# base_board6.net
KiCad netlist of a schematic drawn in EAGLE
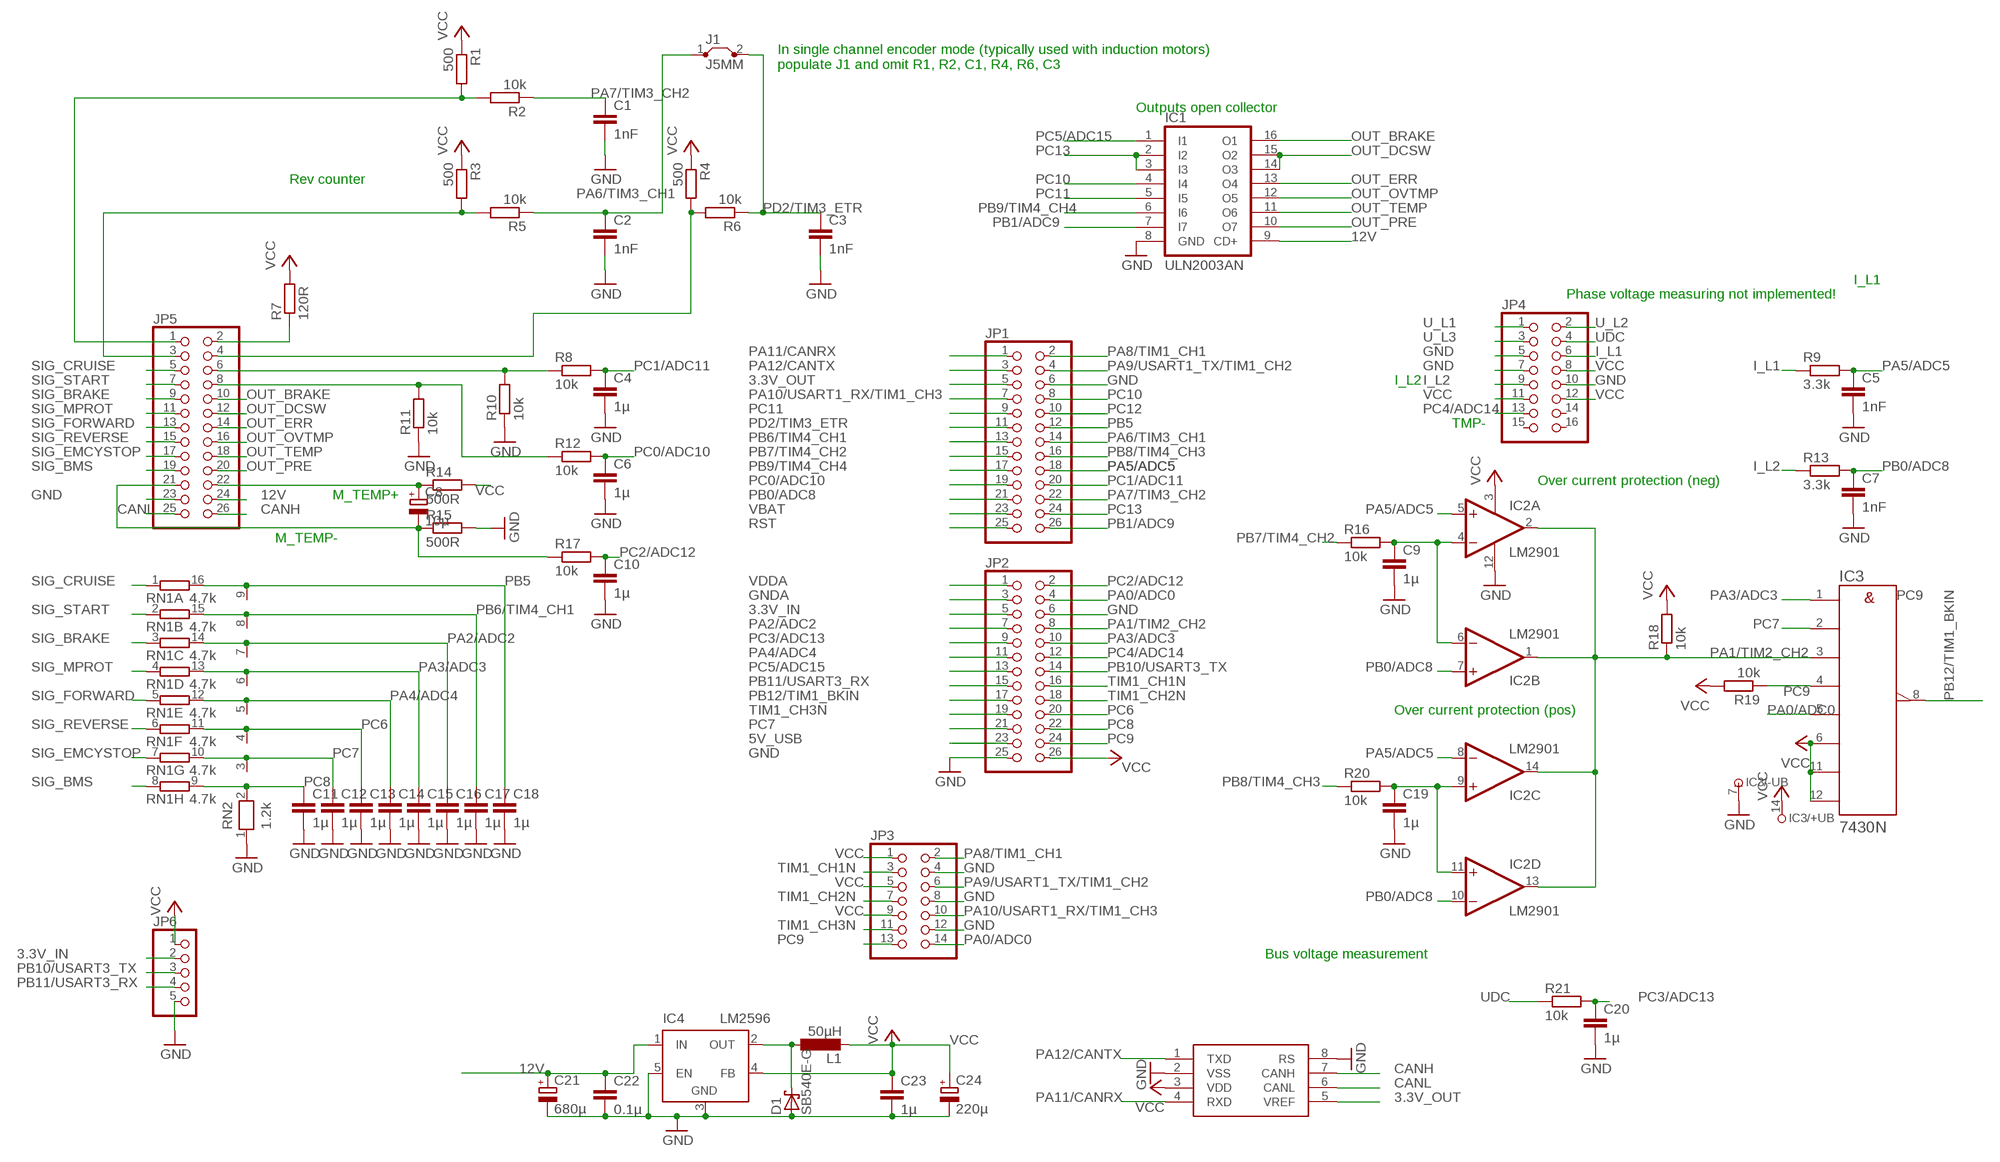
[diagram p0: schematic, sheet 1]

(export (version "E")
  (design (tool "Eeschema 10.0.6"))
  (components
    (comp (ref "C1")
      (value "1nF")
      (footprint "eagle-import:C025-024X044")
      (libsource (lib "eagle-import") (part "C-EU025-024X044"))
    )
    (comp (ref "C2")
      (value "1nF")
      (footprint "eagle-import:C025-024X044")
      (libsource (lib "eagle-import") (part "C-EU025-024X044"))
    )
    (comp (ref "C3")
      (value "1nF")
      (footprint "eagle-import:C025-024X044")
      (libsource (lib "eagle-import") (part "C-EU025-024X044"))
    )
    (comp (ref "C4")
      (value "1µ")
      (footprint "eagle-import:C025-024X044")
      (libsource (lib "eagle-import") (part "C-EU025-024X044"))
    )
    (comp (ref "C5")
      (value "1nF")
      (footprint "eagle-import:C025-024X044")
      (libsource (lib "eagle-import") (part "C-EU025-024X044"))
    )
    (comp (ref "C6")
      (value "1µ")
      (footprint "eagle-import:C025-024X044")
      (libsource (lib "eagle-import") (part "C-EU025-024X044"))
    )
    (comp (ref "C7")
      (value "1nF")
      (footprint "eagle-import:C025-024X044")
      (libsource (lib "eagle-import") (part "C-EU025-024X044"))
    )
    (comp (ref "C8")
      (value "10µ")
      (footprint "eagle-import:E2-4")
      (libsource (lib "eagle-import") (part "CPOL-EUE2-4"))
    )
    (comp (ref "C9")
      (value "1µ")
      (footprint "eagle-import:C025-024X044")
      (libsource (lib "eagle-import") (part "C-EU025-024X044"))
    )
    (comp (ref "C10")
      (value "1µ")
      (footprint "eagle-import:C025-024X044")
      (libsource (lib "eagle-import") (part "C-EU025-024X044"))
    )
    (comp (ref "C11")
      (value "1µ")
      (footprint "eagle-import:C025-024X044")
      (libsource (lib "eagle-import") (part "C-EU025-024X044"))
    )
    (comp (ref "C12")
      (value "1µ")
      (footprint "eagle-import:C025-024X044")
      (libsource (lib "eagle-import") (part "C-EU025-024X044"))
    )
    (comp (ref "C13")
      (value "1µ")
      (footprint "eagle-import:C025-024X044")
      (libsource (lib "eagle-import") (part "C-EU025-024X044"))
    )
    (comp (ref "C14")
      (value "1µ")
      (footprint "eagle-import:C025-024X044")
      (libsource (lib "eagle-import") (part "C-EU025-024X044"))
    )
    (comp (ref "C15")
      (value "1µ")
      (footprint "eagle-import:C025-024X044")
      (libsource (lib "eagle-import") (part "C-EU025-024X044"))
    )
    (comp (ref "C16")
      (value "1µ")
      (footprint "eagle-import:C025-024X044")
      (libsource (lib "eagle-import") (part "C-EU025-024X044"))
    )
    (comp (ref "C17")
      (value "1µ")
      (footprint "eagle-import:C025-024X044")
      (libsource (lib "eagle-import") (part "C-EU025-024X044"))
    )
    (comp (ref "C18")
      (value "1µ")
      (footprint "eagle-import:C025-024X044")
      (libsource (lib "eagle-import") (part "C-EU025-024X044"))
    )
    (comp (ref "C19")
      (value "1µ")
      (footprint "eagle-import:C025-024X044")
      (libsource (lib "eagle-import") (part "C-EU025-024X044"))
    )
    (comp (ref "C20")
      (value "1µ")
      (footprint "eagle-import:C025-024X044")
      (libsource (lib "eagle-import") (part "C-EU025-024X044"))
    )
    (comp (ref "C21")
      (value "680µ")
      (footprint "eagle-import:E2,5-5")
      (libsource (lib "eagle-import") (part "CPOL-EUE2.5-5"))
    )
    (comp (ref "C22")
      (value "0.1µ")
      (footprint "eagle-import:C050-024X044")
      (libsource (lib "eagle-import") (part "C-EU050-024X044"))
    )
    (comp (ref "C23")
      (value "1µ")
      (footprint "eagle-import:C025-024X044")
      (libsource (lib "eagle-import") (part "C-EU025-024X044"))
    )
    (comp (ref "C24")
      (value "220µ")
      (footprint "eagle-import:E2-4")
      (libsource (lib "eagle-import") (part "CPOL-EUE2-4"))
    )
    (comp (ref "D1")
      (value "SB540E-G")
      (footprint "eagle-import:DO201T15")
      (libsource (lib "eagle-import") (part "SCHOTTKY-DIODEDO201T15"))
    )
    (comp (ref "IC1")
      (value "ULN2003AN")
      (footprint "eagle-import:DIL16")
      (libsource (lib "eagle-import") (part "ULN2001AN"))
    )
    (comp (ref "IC2")
      (value "LM2901")
      (footprint "eagle-import:DIL14")
      (libsource (lib "eagle-import") (part "LM339N"))
    )
    (comp (ref "IC3")
      (value "7430N")
      (footprint "eagle-import:DIL14")
      (libsource (lib "eagle-import") (part "7430N"))
    )
    (comp (ref "IC4")
      (value "LM2596")
      (footprint "eagle-import:TO220-51")
      (libsource (lib "eagle-import") (part "LM2596TV"))
    )
    (comp (ref "IC5")
      (value "MCP2562P")
      (footprint "eagle-import:DIL08")
      (libsource (lib "eagle-import") (part "MCP2551P"))
    )
    (comp (ref "J1")
      (value "J5MM")
      (footprint "eagle-import:05")
      (libsource (lib "eagle-import") (part "J5MM"))
    )
    (comp (ref "JP1")
      (value "PINHD-2X13")
      (footprint "eagle-import:2X13")
      (libsource (lib "eagle-import") (part "PINHD-2X13"))
    )
    (comp (ref "JP2")
      (value "PINHD-2X13")
      (footprint "eagle-import:2X13")
      (libsource (lib "eagle-import") (part "PINHD-2X13"))
    )
    (comp (ref "JP3")
      (value "PINHD-2X7")
      (footprint "eagle-import:2X07")
      (libsource (lib "eagle-import") (part "PINHD-2X7"))
    )
    (comp (ref "JP4")
      (value "PINHD-2X8")
      (footprint "eagle-import:2X08")
      (libsource (lib "eagle-import") (part "PINHD-2X8"))
    )
    (comp (ref "JP5")
      (value "PINHD-2X13")
      (footprint "eagle-import:2X13")
      (libsource (lib "eagle-import") (part "PINHD-2X13"))
    )
    (comp (ref "JP6")
      (value "PINHD-1X5")
      (footprint "eagle-import:1X05")
      (libsource (lib "eagle-import") (part "PINHD-1X5"))
    )
    (comp (ref "L1")
      (value "50µH")
      (footprint "eagle-import:TJ3-U1")
      (libsource (lib "eagle-import") (part "L-EUTJ3-U1"))
    )
    (comp (ref "R1")
      (value "500")
      (footprint "eagle-import:0207_10")
      (libsource (lib "eagle-import") (part "R-EU_0207/10"))
    )
    (comp (ref "R2")
      (value "10k")
      (footprint "eagle-import:0207_10")
      (libsource (lib "eagle-import") (part "R-EU_0207/10"))
    )
    (comp (ref "R3")
      (value "500")
      (footprint "eagle-import:0207_10")
      (libsource (lib "eagle-import") (part "R-EU_0207/10"))
    )
    (comp (ref "R4")
      (value "500")
      (footprint "eagle-import:0207_10")
      (libsource (lib "eagle-import") (part "R-EU_0207/10"))
    )
    (comp (ref "R5")
      (value "10k")
      (footprint "eagle-import:0207_10")
      (libsource (lib "eagle-import") (part "R-EU_0207/10"))
    )
    (comp (ref "R6")
      (value "10k")
      (footprint "eagle-import:0207_10")
      (libsource (lib "eagle-import") (part "R-EU_0207/10"))
    )
    (comp (ref "R7")
      (value "120R")
      (footprint "eagle-import:0207_10")
      (libsource (lib "eagle-import") (part "R-EU_0207/10"))
    )
    (comp (ref "R8")
      (value "10k")
      (footprint "eagle-import:0207_10")
      (libsource (lib "eagle-import") (part "R-EU_0207/10"))
    )
    (comp (ref "R9")
      (value "3.3k")
      (footprint "eagle-import:0207_10")
      (libsource (lib "eagle-import") (part "R-EU_0207/10"))
    )
    (comp (ref "R10")
      (value "10k")
      (footprint "eagle-import:0207_10")
      (libsource (lib "eagle-import") (part "R-EU_0207/10"))
    )
    (comp (ref "R11")
      (value "10k")
      (footprint "eagle-import:0207_10")
      (libsource (lib "eagle-import") (part "R-EU_0207/10"))
    )
    (comp (ref "R12")
      (value "10k")
      (footprint "eagle-import:0207_10")
      (libsource (lib "eagle-import") (part "R-EU_0207/10"))
    )
    (comp (ref "R13")
      (value "3.3k")
      (footprint "eagle-import:0207_10")
      (libsource (lib "eagle-import") (part "R-EU_0207/10"))
    )
    (comp (ref "R14")
      (value "500R")
      (footprint "eagle-import:0207_10")
      (libsource (lib "eagle-import") (part "R-EU_0207/10"))
    )
    (comp (ref "R15")
      (value "500R")
      (footprint "eagle-import:0207_10")
      (libsource (lib "eagle-import") (part "R-EU_0207/10"))
    )
    (comp (ref "R16")
      (value "10k")
      (footprint "eagle-import:0207_10")
      (libsource (lib "eagle-import") (part "R-EU_0207/10"))
    )
    (comp (ref "R17")
      (value "10k")
      (footprint "eagle-import:0207_10")
      (libsource (lib "eagle-import") (part "R-EU_0207/10"))
    )
    (comp (ref "R18")
      (value "10k")
      (footprint "eagle-import:0207_10")
      (libsource (lib "eagle-import") (part "R-EU_0207/10"))
    )
    (comp (ref "R19")
      (value "10k")
      (footprint "eagle-import:0207_10")
      (libsource (lib "eagle-import") (part "R-EU_0207/10"))
    )
    (comp (ref "R20")
      (value "10k")
      (footprint "eagle-import:0207_10")
      (libsource (lib "eagle-import") (part "R-EU_0207/10"))
    )
    (comp (ref "R21")
      (value "10k")
      (footprint "eagle-import:0207_10")
      (libsource (lib "eagle-import") (part "R-EU_0207/10"))
    )
    (comp (ref "RN1")
      (value "4.7k")
      (footprint "eagle-import:DIL16")
      (libsource (lib "eagle-import") (part "8R-N"))
    )
    (comp (ref "RN2")
      (value "1.2k")
      (footprint "eagle-import:RN-9")
      (libsource (lib "eagle-import") (part "RN08"))
    )
  )
  (nets
    (net (code "1") (name "/3.3V_IN") (class "Default")
      (node (ref "JP2") (pin "5") (pinfunction "5_5") (pintype "passive"))
      (node (ref "JP6") (pin "2") (pinfunction "2_2") (pintype "passive"))
    )
    (net (code "2") (name "/3.3V_OUT") (class "Default")
      (node (ref "IC5") (pin "5") (pinfunction "VREF_5") (pintype "bidirectional"))
      (node (ref "JP1") (pin "5") (pinfunction "5_5") (pintype "passive"))
    )
    (net (code "3") (name "/5V_USB") (class "Default")
      (node (ref "JP2") (pin "23") (pinfunction "23_23") (pintype "passive"))
    )
    (net (code "4") (name "/12V") (class "Default")
      (node (ref "C21") (pin "+") (pinfunction "+_+") (pintype "passive"))
      (node (ref "C22") (pin "1") (pinfunction "1_1") (pintype "passive"))
      (node (ref "IC1") (pin "9") (pinfunction "CD+_9") (pintype "passive"))
      (node (ref "IC4") (pin "1") (pinfunction "IN_1") (pintype "input"))
      (node (ref "JP5") (pin "24") (pinfunction "24_24") (pintype "passive"))
    )
    (net (code "5") (name "/CANH") (class "Default")
      (node (ref "IC5") (pin "7") (pinfunction "CANH_7") (pintype "bidirectional"))
      (node (ref "JP5") (pin "26") (pinfunction "26_26") (pintype "passive"))
    )
    (net (code "6") (name "/CANL") (class "Default")
      (node (ref "IC5") (pin "6") (pinfunction "CANL_6") (pintype "bidirectional"))
      (node (ref "JP5") (pin "25") (pinfunction "25_25") (pintype "passive"))
    )
    (net (code "7") (name "/GNDA") (class "Default")
      (node (ref "JP2") (pin "3") (pinfunction "3_3") (pintype "passive"))
    )
    (net (code "8") (name "/I_L1") (class "Default")
      (node (ref "JP4") (pin "6") (pinfunction "6_6") (pintype "passive"))
      (node (ref "R9") (pin "1") (pinfunction "1_1") (pintype "passive"))
    )
    (net (code "9") (name "/I_L2") (class "Default")
      (node (ref "JP4") (pin "9") (pinfunction "9_9") (pintype "passive"))
      (node (ref "R13") (pin "1") (pinfunction "1_1") (pintype "passive"))
    )
    (net (code "10") (name "/OUT_BRAKE") (class "Default")
      (node (ref "IC1") (pin "16") (pinfunction "O1_16") (pintype "open_collector"))
      (node (ref "JP5") (pin "10") (pinfunction "10_10") (pintype "passive"))
    )
    (net (code "11") (name "/OUT_DCSW") (class "Default")
      (node (ref "IC1") (pin "14") (pinfunction "O3_14") (pintype "open_collector"))
      (node (ref "IC1") (pin "15") (pinfunction "O2_15") (pintype "open_collector"))
      (node (ref "JP5") (pin "12") (pinfunction "12_12") (pintype "passive"))
    )
    (net (code "12") (name "/OUT_ERR") (class "Default")
      (node (ref "IC1") (pin "13") (pinfunction "O4_13") (pintype "open_collector"))
      (node (ref "JP5") (pin "14") (pinfunction "14_14") (pintype "passive"))
    )
    (net (code "13") (name "/OUT_OVTMP") (class "Default")
      (node (ref "IC1") (pin "12") (pinfunction "O5_12") (pintype "open_collector"))
      (node (ref "JP5") (pin "16") (pinfunction "16_16") (pintype "passive"))
    )
    (net (code "14") (name "/OUT_PRE") (class "Default")
      (node (ref "IC1") (pin "10") (pinfunction "O7_10") (pintype "open_collector"))
      (node (ref "JP5") (pin "20") (pinfunction "20_20") (pintype "passive"))
    )
    (net (code "15") (name "/OUT_TEMP") (class "Default")
      (node (ref "IC1") (pin "11") (pinfunction "O6_11") (pintype "open_collector"))
      (node (ref "JP5") (pin "18") (pinfunction "18_18") (pintype "passive"))
    )
    (net (code "16") (name "/PA0{slash}ADC0") (class "Default")
      (node (ref "IC3") (pin "5") (pinfunction "E_5") (pintype "input"))
      (node (ref "JP2") (pin "4") (pinfunction "4_4") (pintype "passive"))
      (node (ref "JP3") (pin "14") (pinfunction "14_14") (pintype "passive"))
    )
    (net (code "17") (name "/PA1{slash}TIM2_CH2") (class "Default")
      (node (ref "IC2") (pin "1") (pinfunction "OUT_1") (pintype "open_collector"))
      (node (ref "IC2") (pin "13") (pinfunction "OUT_13") (pintype "open_collector"))
      (node (ref "IC2") (pin "14") (pinfunction "OUT_14") (pintype "open_collector"))
      (node (ref "IC2") (pin "2") (pinfunction "OUT_2") (pintype "open_collector"))
      (node (ref "IC3") (pin "3") (pinfunction "C_3") (pintype "input"))
      (node (ref "JP2") (pin "8") (pinfunction "8_8") (pintype "passive"))
      (node (ref "R18") (pin "1") (pinfunction "1_1") (pintype "passive"))
    )
    (net (code "18") (name "/PA2{slash}ADC2") (class "Default")
      (node (ref "C16") (pin "1") (pinfunction "1_1") (pintype "passive"))
      (node (ref "JP2") (pin "7") (pinfunction "7_7") (pintype "passive"))
      (node (ref "RN1") (pin "14") (pinfunction "2_14") (pintype "passive"))
      (node (ref "RN2") (pin "7") (pinfunction "7_7") (pintype "passive"))
    )
    (net (code "19") (name "/PA3{slash}ADC3") (class "Default")
      (node (ref "C15") (pin "1") (pinfunction "1_1") (pintype "passive"))
      (node (ref "IC3") (pin "1") (pinfunction "A_1") (pintype "input"))
      (node (ref "JP2") (pin "10") (pinfunction "10_10") (pintype "passive"))
      (node (ref "RN1") (pin "13") (pinfunction "2_13") (pintype "passive"))
      (node (ref "RN2") (pin "6") (pinfunction "6_6") (pintype "passive"))
    )
    (net (code "20") (name "/PA4{slash}ADC4") (class "Default")
      (node (ref "C14") (pin "1") (pinfunction "1_1") (pintype "passive"))
      (node (ref "JP2") (pin "11") (pinfunction "11_11") (pintype "passive"))
      (node (ref "RN1") (pin "12") (pinfunction "2_12") (pintype "passive"))
      (node (ref "RN2") (pin "5") (pinfunction "5_5") (pintype "passive"))
    )
    (net (code "21") (name "/PA5{slash}ADC5") (class "Default")
      (node (ref "C5") (pin "1") (pinfunction "1_1") (pintype "passive"))
      (node (ref "IC2") (pin "5") (pinfunction "+IN_5") (pintype "input"))
      (node (ref "IC2") (pin "8") (pinfunction "-IN_8") (pintype "input"))
      (node (ref "JP1") (pin "18") (pinfunction "18_18") (pintype "passive"))
      (node (ref "R9") (pin "2") (pinfunction "2_2") (pintype "passive"))
    )
    (net (code "22") (name "/PA6{slash}TIM3_CH1") (class "Default")
      (node (ref "C2") (pin "1") (pinfunction "1_1") (pintype "passive"))
      (node (ref "J1") (pin "1") (pinfunction "1_1") (pintype "passive"))
      (node (ref "JP1") (pin "14") (pinfunction "14_14") (pintype "passive"))
      (node (ref "R5") (pin "1") (pinfunction "1_1") (pintype "passive"))
    )
    (net (code "23") (name "/PA7{slash}TIM3_CH2") (class "Default")
      (node (ref "C1") (pin "1") (pinfunction "1_1") (pintype "passive"))
      (node (ref "JP1") (pin "22") (pinfunction "22_22") (pintype "passive"))
      (node (ref "R2") (pin "1") (pinfunction "1_1") (pintype "passive"))
    )
    (net (code "24") (name "/PA8{slash}TIM1_CH1") (class "Default")
      (node (ref "JP1") (pin "2") (pinfunction "2_2") (pintype "passive"))
      (node (ref "JP3") (pin "2") (pinfunction "2_2") (pintype "passive"))
    )
    (net (code "25") (name "/PA9{slash}USART1_TX{slash}TIM1_CH2") (class "Default")
      (node (ref "JP1") (pin "4") (pinfunction "4_4") (pintype "passive"))
      (node (ref "JP3") (pin "6") (pinfunction "6_6") (pintype "passive"))
    )
    (net (code "26") (name "/PA10{slash}USART1_RX{slash}TIM1_CH3") (class "Default")
      (node (ref "JP1") (pin "7") (pinfunction "7_7") (pintype "passive"))
      (node (ref "JP3") (pin "10") (pinfunction "10_10") (pintype "passive"))
    )
    (net (code "27") (name "/PA11{slash}CANRX") (class "Default")
      (node (ref "IC5") (pin "4") (pinfunction "RXD_4") (pintype "bidirectional"))
      (node (ref "JP1") (pin "1") (pinfunction "1_1") (pintype "passive"))
    )
    (net (code "28") (name "/PA12{slash}CANTX") (class "Default")
      (node (ref "IC5") (pin "1") (pinfunction "TXD_1") (pintype "bidirectional"))
      (node (ref "JP1") (pin "3") (pinfunction "3_3") (pintype "passive"))
    )
    (net (code "29") (name "/PB0{slash}ADC8") (class "Default")
      (node (ref "C7") (pin "1") (pinfunction "1_1") (pintype "passive"))
      (node (ref "IC2") (pin "10") (pinfunction "-IN_10") (pintype "input"))
      (node (ref "IC2") (pin "7") (pinfunction "+IN_7") (pintype "input"))
      (node (ref "JP1") (pin "21") (pinfunction "21_21") (pintype "passive"))
      (node (ref "R13") (pin "2") (pinfunction "2_2") (pintype "passive"))
    )
    (net (code "30") (name "/PB1{slash}ADC9") (class "Default")
      (node (ref "IC1") (pin "7") (pinfunction "I7_7") (pintype "input"))
      (node (ref "JP1") (pin "26") (pinfunction "26_26") (pintype "passive"))
    )
    (net (code "31") (name "/PB5") (class "Default")
      (node (ref "C18") (pin "1") (pinfunction "1_1") (pintype "passive"))
      (node (ref "JP1") (pin "12") (pinfunction "12_12") (pintype "passive"))
      (node (ref "RN1") (pin "16") (pinfunction "2_16") (pintype "passive"))
      (node (ref "RN2") (pin "9") (pinfunction "9_9") (pintype "passive"))
    )
    (net (code "32") (name "/PB6{slash}TIM4_CH1") (class "Default")
      (node (ref "C17") (pin "1") (pinfunction "1_1") (pintype "passive"))
      (node (ref "JP1") (pin "13") (pinfunction "13_13") (pintype "passive"))
      (node (ref "RN1") (pin "15") (pinfunction "2_15") (pintype "passive"))
      (node (ref "RN2") (pin "8") (pinfunction "8_8") (pintype "passive"))
    )
    (net (code "33") (name "/PB7{slash}TIM4_CH2") (class "Default")
      (node (ref "JP1") (pin "15") (pinfunction "15_15") (pintype "passive"))
      (node (ref "R16") (pin "1") (pinfunction "1_1") (pintype "passive"))
    )
    (net (code "34") (name "/PB8{slash}TIM4_CH3") (class "Default")
      (node (ref "JP1") (pin "16") (pinfunction "16_16") (pintype "passive"))
      (node (ref "R20") (pin "1") (pinfunction "1_1") (pintype "passive"))
    )
    (net (code "35") (name "/PB9{slash}TIM4_CH4") (class "Default")
      (node (ref "IC1") (pin "6") (pinfunction "I6_6") (pintype "input"))
      (node (ref "JP1") (pin "17") (pinfunction "17_17") (pintype "passive"))
    )
    (net (code "36") (name "/PB10{slash}USART3_TX") (class "Default")
      (node (ref "JP2") (pin "14") (pinfunction "14_14") (pintype "passive"))
      (node (ref "JP6") (pin "3") (pinfunction "3_3") (pintype "passive"))
    )
    (net (code "37") (name "/PB11{slash}USART3_RX") (class "Default")
      (node (ref "JP2") (pin "15") (pinfunction "15_15") (pintype "passive"))
      (node (ref "JP6") (pin "4") (pinfunction "4_4") (pintype "passive"))
    )
    (net (code "38") (name "/PB12{slash}TIM1_BKIN") (class "Default")
      (node (ref "IC3") (pin "8") (pinfunction "Y_8") (pintype "output"))
      (node (ref "JP2") (pin "17") (pinfunction "17_17") (pintype "passive"))
    )
    (net (code "39") (name "/PC0{slash}ADC10") (class "Default")
      (node (ref "C6") (pin "1") (pinfunction "1_1") (pintype "passive"))
      (node (ref "JP1") (pin "19") (pinfunction "19_19") (pintype "passive"))
      (node (ref "R12") (pin "2") (pinfunction "2_2") (pintype "passive"))
    )
    (net (code "40") (name "/PC1{slash}ADC11") (class "Default")
      (node (ref "C4") (pin "1") (pinfunction "1_1") (pintype "passive"))
      (node (ref "JP1") (pin "20") (pinfunction "20_20") (pintype "passive"))
      (node (ref "R8") (pin "2") (pinfunction "2_2") (pintype "passive"))
    )
    (net (code "41") (name "/PC2{slash}ADC12") (class "Default")
      (node (ref "C10") (pin "1") (pinfunction "1_1") (pintype "passive"))
      (node (ref "JP2") (pin "2") (pinfunction "2_2") (pintype "passive"))
      (node (ref "R17") (pin "2") (pinfunction "2_2") (pintype "passive"))
    )
    (net (code "42") (name "/PC3{slash}ADC13") (class "Default")
      (node (ref "C20") (pin "1") (pinfunction "1_1") (pintype "passive"))
      (node (ref "JP2") (pin "9") (pinfunction "9_9") (pintype "passive"))
      (node (ref "R21") (pin "2") (pinfunction "2_2") (pintype "passive"))
    )
    (net (code "43") (name "/PC4{slash}ADC14") (class "Default")
      (node (ref "JP2") (pin "12") (pinfunction "12_12") (pintype "passive"))
      (node (ref "JP4") (pin "13") (pinfunction "13_13") (pintype "passive"))
    )
    (net (code "44") (name "/PC5{slash}ADC15") (class "Default")
      (node (ref "IC1") (pin "1") (pinfunction "I1_1") (pintype "input"))
      (node (ref "JP2") (pin "13") (pinfunction "13_13") (pintype "passive"))
    )
    (net (code "45") (name "/PC6") (class "Default")
      (node (ref "C13") (pin "1") (pinfunction "1_1") (pintype "passive"))
      (node (ref "JP2") (pin "20") (pinfunction "20_20") (pintype "passive"))
      (node (ref "RN1") (pin "11") (pinfunction "2_11") (pintype "passive"))
      (node (ref "RN2") (pin "4") (pinfunction "4_4") (pintype "passive"))
    )
    (net (code "46") (name "/PC7") (class "Default")
      (node (ref "C12") (pin "1") (pinfunction "1_1") (pintype "passive"))
      (node (ref "IC3") (pin "2") (pinfunction "B_2") (pintype "input"))
      (node (ref "JP2") (pin "21") (pinfunction "21_21") (pintype "passive"))
      (node (ref "RN1") (pin "10") (pinfunction "2_10") (pintype "passive"))
      (node (ref "RN2") (pin "3") (pinfunction "3_3") (pintype "passive"))
    )
    (net (code "47") (name "/PC8") (class "Default")
      (node (ref "C11") (pin "1") (pinfunction "1_1") (pintype "passive"))
      (node (ref "JP2") (pin "22") (pinfunction "22_22") (pintype "passive"))
      (node (ref "RN1") (pin "9") (pinfunction "2_9") (pintype "passive"))
      (node (ref "RN2") (pin "2") (pinfunction "2_2") (pintype "passive"))
    )
    (net (code "48") (name "/PC9") (class "Default")
      (node (ref "IC3") (pin "4") (pinfunction "D_4") (pintype "input"))
      (node (ref "JP2") (pin "24") (pinfunction "24_24") (pintype "passive"))
      (node (ref "JP3") (pin "13") (pinfunction "13_13") (pintype "passive"))
      (node (ref "R19") (pin "1") (pinfunction "1_1") (pintype "passive"))
    )
    (net (code "49") (name "/PC10") (class "Default")
      (node (ref "IC1") (pin "4") (pinfunction "I4_4") (pintype "input"))
      (node (ref "JP1") (pin "8") (pinfunction "8_8") (pintype "passive"))
    )
    (net (code "50") (name "/PC11") (class "Default")
      (node (ref "IC1") (pin "5") (pinfunction "I5_5") (pintype "input"))
      (node (ref "JP1") (pin "9") (pinfunction "9_9") (pintype "passive"))
    )
    (net (code "51") (name "/PC12") (class "Default")
      (node (ref "JP1") (pin "10") (pinfunction "10_10") (pintype "passive"))
    )
    (net (code "52") (name "/PC13") (class "Default")
      (node (ref "IC1") (pin "2") (pinfunction "I2_2") (pintype "input"))
      (node (ref "IC1") (pin "3") (pinfunction "I3_3") (pintype "input"))
      (node (ref "JP1") (pin "24") (pinfunction "24_24") (pintype "passive"))
    )
    (net (code "53") (name "/PD2{slash}TIM3_ETR") (class "Default")
      (node (ref "C3") (pin "1") (pinfunction "1_1") (pintype "passive"))
      (node (ref "J1") (pin "2") (pinfunction "2_2") (pintype "passive"))
      (node (ref "JP1") (pin "11") (pinfunction "11_11") (pintype "passive"))
      (node (ref "R6") (pin "1") (pinfunction "1_1") (pintype "passive"))
    )
    (net (code "54") (name "/RST") (class "Default")
      (node (ref "JP1") (pin "25") (pinfunction "25_25") (pintype "passive"))
    )
    (net (code "55") (name "/SIG_BMS") (class "Default")
      (node (ref "JP5") (pin "19") (pinfunction "19_19") (pintype "passive"))
      (node (ref "RN1") (pin "8") (pinfunction "1_8") (pintype "passive"))
    )
    (net (code "56") (name "/SIG_BRAKE") (class "Default")
      (node (ref "JP5") (pin "9") (pinfunction "9_9") (pintype "passive"))
      (node (ref "RN1") (pin "3") (pinfunction "1_3") (pintype "passive"))
    )
    (net (code "57") (name "/SIG_CRUISE") (class "Default")
      (node (ref "JP5") (pin "5") (pinfunction "5_5") (pintype "passive"))
      (node (ref "RN1") (pin "1") (pinfunction "1_1") (pintype "passive"))
    )
    (net (code "58") (name "/SIG_EMCYSTOP") (class "Default")
      (node (ref "JP5") (pin "17") (pinfunction "17_17") (pintype "passive"))
      (node (ref "RN1") (pin "7") (pinfunction "1_7") (pintype "passive"))
    )
    (net (code "59") (name "/SIG_FORWARD") (class "Default")
      (node (ref "JP5") (pin "13") (pinfunction "13_13") (pintype "passive"))
      (node (ref "RN1") (pin "5") (pinfunction "1_5") (pintype "passive"))
    )
    (net (code "60") (name "/SIG_MPROT") (class "Default")
      (node (ref "JP5") (pin "11") (pinfunction "11_11") (pintype "passive"))
      (node (ref "RN1") (pin "4") (pinfunction "1_4") (pintype "passive"))
    )
    (net (code "61") (name "/SIG_REVERSE") (class "Default")
      (node (ref "JP5") (pin "15") (pinfunction "15_15") (pintype "passive"))
      (node (ref "RN1") (pin "6") (pinfunction "1_6") (pintype "passive"))
    )
    (net (code "62") (name "/SIG_START") (class "Default")
      (node (ref "JP5") (pin "7") (pinfunction "7_7") (pintype "passive"))
      (node (ref "RN1") (pin "2") (pinfunction "1_2") (pintype "passive"))
    )
    (net (code "63") (name "/TIM1_CH1N") (class "Default")
      (node (ref "JP2") (pin "16") (pinfunction "16_16") (pintype "passive"))
      (node (ref "JP3") (pin "3") (pinfunction "3_3") (pintype "passive"))
    )
    (net (code "64") (name "/TIM1_CH2N") (class "Default")
      (node (ref "JP2") (pin "18") (pinfunction "18_18") (pintype "passive"))
      (node (ref "JP3") (pin "7") (pinfunction "7_7") (pintype "passive"))
    )
    (net (code "65") (name "/TIM1_CH3N") (class "Default")
      (node (ref "JP2") (pin "19") (pinfunction "19_19") (pintype "passive"))
      (node (ref "JP3") (pin "11") (pinfunction "11_11") (pintype "passive"))
    )
    (net (code "66") (name "/UDC") (class "Default")
      (node (ref "JP4") (pin "4") (pinfunction "4_4") (pintype "passive"))
      (node (ref "R21") (pin "1") (pinfunction "1_1") (pintype "passive"))
    )
    (net (code "67") (name "/U_L1") (class "Default")
      (node (ref "JP4") (pin "1") (pinfunction "1_1") (pintype "passive"))
    )
    (net (code "68") (name "/U_L2") (class "Default")
      (node (ref "JP4") (pin "2") (pinfunction "2_2") (pintype "passive"))
    )
    (net (code "69") (name "/U_L3") (class "Default")
      (node (ref "JP4") (pin "3") (pinfunction "3_3") (pintype "passive"))
    )
    (net (code "70") (name "/VBAT") (class "Default")
      (node (ref "JP1") (pin "23") (pinfunction "23_23") (pintype "passive"))
    )
    (net (code "71") (name "/VDDA") (class "Default")
      (node (ref "JP2") (pin "1") (pinfunction "1_1") (pintype "passive"))
    )
    (net (code "72") (name "GND") (class "Default")
      (node (ref "C1") (pin "2") (pinfunction "2_2") (pintype "passive"))
      (node (ref "C10") (pin "2") (pinfunction "2_2") (pintype "passive"))
      (node (ref "C11") (pin "2") (pinfunction "2_2") (pintype "passive"))
      (node (ref "C12") (pin "2") (pinfunction "2_2") (pintype "passive"))
      (node (ref "C13") (pin "2") (pinfunction "2_2") (pintype "passive"))
      (node (ref "C14") (pin "2") (pinfunction "2_2") (pintype "passive"))
      (node (ref "C15") (pin "2") (pinfunction "2_2") (pintype "passive"))
      (node (ref "C16") (pin "2") (pinfunction "2_2") (pintype "passive"))
      (node (ref "C17") (pin "2") (pinfunction "2_2") (pintype "passive"))
      (node (ref "C18") (pin "2") (pinfunction "2_2") (pintype "passive"))
      (node (ref "C19") (pin "2") (pinfunction "2_2") (pintype "passive"))
      (node (ref "C2") (pin "2") (pinfunction "2_2") (pintype "passive"))
      (node (ref "C20") (pin "2") (pinfunction "2_2") (pintype "passive"))
      (node (ref "C21") (pin "-") (pinfunction "-_-") (pintype "passive"))
      (node (ref "C22") (pin "2") (pinfunction "2_2") (pintype "passive"))
      (node (ref "C23") (pin "2") (pinfunction "2_2") (pintype "passive"))
      (node (ref "C24") (pin "-") (pinfunction "-_-") (pintype "passive"))
      (node (ref "C3") (pin "2") (pinfunction "2_2") (pintype "passive"))
      (node (ref "C4") (pin "2") (pinfunction "2_2") (pintype "passive"))
      (node (ref "C5") (pin "2") (pinfunction "2_2") (pintype "passive"))
      (node (ref "C6") (pin "2") (pinfunction "2_2") (pintype "passive"))
      (node (ref "C7") (pin "2") (pinfunction "2_2") (pintype "passive"))
      (node (ref "C9") (pin "2") (pinfunction "2_2") (pintype "passive"))
      (node (ref "D1") (pin "A") (pinfunction "A_A") (pintype "passive"))
      (node (ref "IC1") (pin "8") (pinfunction "GND_8") (pintype "power_in"))
      (node (ref "IC2") (pin "12") (pinfunction "GND_12") (pintype "power_in"))
      (node (ref "IC3") (pin "7") (pinfunction "-UB_7") (pintype "power_in"))
      (node (ref "IC4") (pin "3") (pinfunction "GND_3") (pintype "power_in"))
      (node (ref "IC4") (pin "5") (pinfunction "EN_5") (pintype "input"))
      (node (ref "IC5") (pin "2") (pinfunction "VSS_2") (pintype "bidirectional"))
      (node (ref "IC5") (pin "8") (pinfunction "RS_8") (pintype "bidirectional"))
      (node (ref "JP1") (pin "6") (pinfunction "6_6") (pintype "passive"))
      (node (ref "JP2") (pin "25") (pinfunction "25_25") (pintype "passive"))
      (node (ref "JP2") (pin "6") (pinfunction "6_6") (pintype "passive"))
      (node (ref "JP3") (pin "12") (pinfunction "12_12") (pintype "passive"))
      (node (ref "JP3") (pin "4") (pinfunction "4_4") (pintype "passive"))
      (node (ref "JP3") (pin "8") (pinfunction "8_8") (pintype "passive"))
      (node (ref "JP4") (pin "10") (pinfunction "10_10") (pintype "passive"))
      (node (ref "JP4") (pin "5") (pinfunction "5_5") (pintype "passive"))
      (node (ref "JP4") (pin "7") (pinfunction "7_7") (pintype "passive"))
      (node (ref "JP5") (pin "23") (pinfunction "23_23") (pintype "passive"))
      (node (ref "JP6") (pin "5") (pinfunction "5_5") (pintype "passive"))
      (node (ref "R10") (pin "1") (pinfunction "1_1") (pintype "passive"))
      (node (ref "R11") (pin "1") (pinfunction "1_1") (pintype "passive"))
      (node (ref "R15") (pin "2") (pinfunction "2_2") (pintype "passive"))
      (node (ref "RN2") (pin "1") (pinfunction "1_1") (pintype "passive"))
    )
    (net (code "73") (name "Net-(C8-Pad+)") (class "Default")
      (node (ref "C8") (pin "+") (pinfunction "+_+") (pintype "passive"))
      (node (ref "JP5") (pin "22") (pinfunction "22_22") (pintype "passive"))
      (node (ref "R14") (pin "1") (pinfunction "1_1") (pintype "passive"))
    )
    (net (code "74") (name "Net-(C8-Pad-)") (class "Default")
      (node (ref "C8") (pin "-") (pinfunction "-_-") (pintype "passive"))
      (node (ref "JP5") (pin "21") (pinfunction "21_21") (pintype "passive"))
      (node (ref "R15") (pin "1") (pinfunction "1_1") (pintype "passive"))
      (node (ref "R17") (pin "1") (pinfunction "1_1") (pintype "passive"))
    )
    (net (code "75") (name "Net-(IC2A--IN)") (class "Default")
      (node (ref "C9") (pin "1") (pinfunction "1_1") (pintype "passive"))
      (node (ref "IC2") (pin "4") (pinfunction "-IN_4") (pintype "input"))
      (node (ref "IC2") (pin "6") (pinfunction "-IN_6") (pintype "input"))
      (node (ref "R16") (pin "2") (pinfunction "2_2") (pintype "passive"))
    )
    (net (code "76") (name "Net-(IC2C-+IN)") (class "Default")
      (node (ref "C19") (pin "1") (pinfunction "1_1") (pintype "passive"))
      (node (ref "IC2") (pin "11") (pinfunction "+IN_11") (pintype "input"))
      (node (ref "IC2") (pin "9") (pinfunction "+IN_9") (pintype "input"))
      (node (ref "R20") (pin "2") (pinfunction "2_2") (pintype "passive"))
    )
    (net (code "77") (name "Net-(IC4-OUT)") (class "Default")
      (node (ref "D1") (pin "C") (pinfunction "C_C") (pintype "passive"))
      (node (ref "IC4") (pin "2") (pinfunction "OUT_2") (pintype "output"))
      (node (ref "L1") (pin "1") (pinfunction "1_1") (pintype "passive"))
    )
    (net (code "78") (name "Net-(JP5-Pad1)") (class "Default")
      (node (ref "JP5") (pin "1") (pinfunction "1_1") (pintype "passive"))
      (node (ref "R1") (pin "2") (pinfunction "2_2") (pintype "passive"))
      (node (ref "R2") (pin "2") (pinfunction "2_2") (pintype "passive"))
    )
    (net (code "79") (name "Net-(JP5-Pad2)") (class "Default")
      (node (ref "JP5") (pin "2") (pinfunction "2_2") (pintype "passive"))
      (node (ref "R7") (pin "1") (pinfunction "1_1") (pintype "passive"))
    )
    (net (code "80") (name "Net-(JP5-Pad3)") (class "Default")
      (node (ref "JP5") (pin "3") (pinfunction "3_3") (pintype "passive"))
      (node (ref "R3") (pin "2") (pinfunction "2_2") (pintype "passive"))
      (node (ref "R5") (pin "2") (pinfunction "2_2") (pintype "passive"))
    )
    (net (code "81") (name "Net-(JP5-Pad4)") (class "Default")
      (node (ref "JP5") (pin "4") (pinfunction "4_4") (pintype "passive"))
      (node (ref "R4") (pin "2") (pinfunction "2_2") (pintype "passive"))
      (node (ref "R6") (pin "2") (pinfunction "2_2") (pintype "passive"))
    )
    (net (code "82") (name "Net-(JP5-Pad6)") (class "Default")
      (node (ref "JP5") (pin "6") (pinfunction "6_6") (pintype "passive"))
      (node (ref "R10") (pin "2") (pinfunction "2_2") (pintype "passive"))
      (node (ref "R8") (pin "1") (pinfunction "1_1") (pintype "passive"))
    )
    (net (code "83") (name "Net-(JP5-Pad8)") (class "Default")
      (node (ref "JP5") (pin "8") (pinfunction "8_8") (pintype "passive"))
      (node (ref "R11") (pin "2") (pinfunction "2_2") (pintype "passive"))
      (node (ref "R12") (pin "1") (pinfunction "1_1") (pintype "passive"))
    )
    (net (code "84") (name "VCC") (class "Default")
      (node (ref "C23") (pin "1") (pinfunction "1_1") (pintype "passive"))
      (node (ref "C24") (pin "+") (pinfunction "+_+") (pintype "passive"))
      (node (ref "IC2") (pin "3") (pinfunction "V+_3") (pintype "power_in"))
      (node (ref "IC3") (pin "11") (pinfunction "G_11") (pintype "input"))
      (node (ref "IC3") (pin "12") (pinfunction "H_12") (pintype "input"))
      (node (ref "IC3") (pin "14") (pinfunction "+UB_14") (pintype "power_in"))
      (node (ref "IC3") (pin "6") (pinfunction "F_6") (pintype "input"))
      (node (ref "IC4") (pin "4") (pinfunction "FB_4") (pintype "input"))
      (node (ref "IC5") (pin "3") (pinfunction "VDD_3") (pintype "bidirectional"))
      (node (ref "JP2") (pin "26") (pinfunction "26_26") (pintype "passive"))
      (node (ref "JP3") (pin "1") (pinfunction "1_1") (pintype "passive"))
      (node (ref "JP3") (pin "5") (pinfunction "5_5") (pintype "passive"))
      (node (ref "JP3") (pin "9") (pinfunction "9_9") (pintype "passive"))
      (node (ref "JP4") (pin "11") (pinfunction "11_11") (pintype "passive"))
      (node (ref "JP4") (pin "12") (pinfunction "12_12") (pintype "passive"))
      (node (ref "JP4") (pin "8") (pinfunction "8_8") (pintype "passive"))
      (node (ref "JP6") (pin "1") (pinfunction "1_1") (pintype "passive"))
      (node (ref "L1") (pin "2") (pinfunction "2_2") (pintype "passive"))
      (node (ref "R1") (pin "1") (pinfunction "1_1") (pintype "passive"))
      (node (ref "R14") (pin "2") (pinfunction "2_2") (pintype "passive"))
      (node (ref "R18") (pin "2") (pinfunction "2_2") (pintype "passive"))
      (node (ref "R19") (pin "2") (pinfunction "2_2") (pintype "passive"))
      (node (ref "R3") (pin "1") (pinfunction "1_1") (pintype "passive"))
      (node (ref "R4") (pin "1") (pinfunction "1_1") (pintype "passive"))
      (node (ref "R7") (pin "2") (pinfunction "2_2") (pintype "passive"))
    )
    (net (code "85") (name "unconnected-(JP4-Pad14)") (class "Default")
      (node (ref "JP4") (pin "14") (pinfunction "14_14") (pintype "passive"))
    )
    (net (code "86") (name "unconnected-(JP4-Pad15)") (class "Default")
      (node (ref "JP4") (pin "15") (pinfunction "15_15") (pintype "passive"))
    )
    (net (code "87") (name "unconnected-(JP4-Pad16)") (class "Default")
      (node (ref "JP4") (pin "16") (pinfunction "16_16") (pintype "passive"))
    )
  )
)
